# 03_CORE_BOARD.net
KiCad netlist of a schematic drawn in Altium Designer
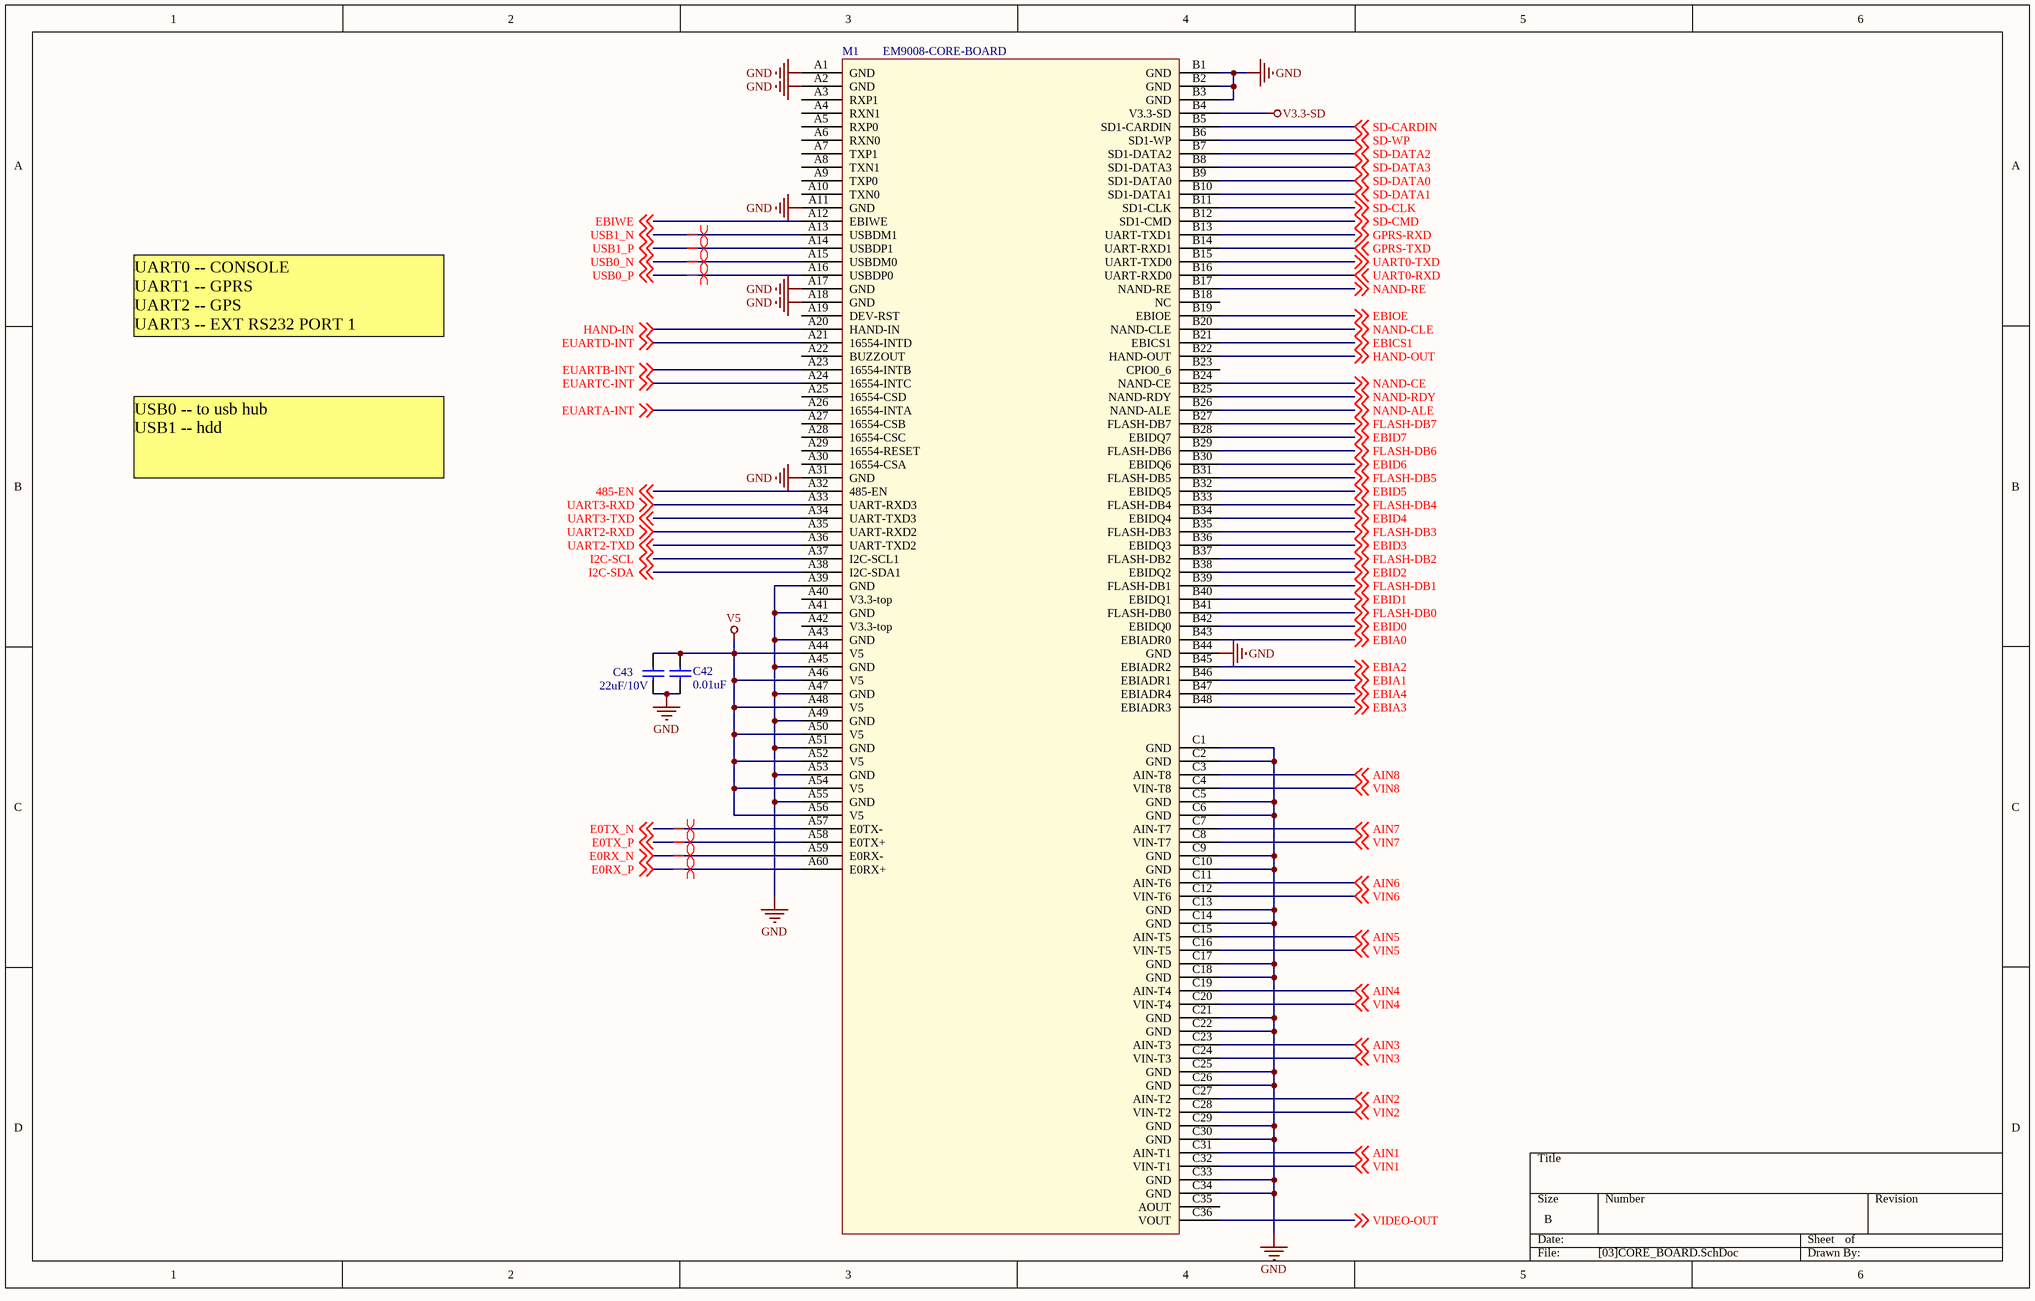
[diagram p0: [03]CORE_BOARD.SchDoc]

(export (version "E")
  (design (tool "Eeschema 10.0.6"))
  (components
    (comp (ref "C42")
      (value "0.01uF")
      (footprint "0603")
      (description "Capacitor")
      (libsource (lib "Miscellaneous Devices") (part "Cap"))
    )
    (comp (ref "C43")
      (value "22uF/10V")
      (footprint "1210")
      (description "Capacitor")
      (libsource (lib "Miscellaneous Devices") (part "Cap"))
    )
    (comp (ref "M1")
      (value "EM9008-CORE-BOARD")
      (footprint "EM9008")
      (libsource (lib "Schlib") (part "EM9008-CORE-BOARD"))
    )
  )
  (nets
    (net (code "1") (name "485-EN") (class "Default")
      (node (ref "M1") (pin "A32") (pinfunction "485-EN_A32") (pintype "passive"))
    )
    (net (code "2") (name "AIN1") (class "Default")
      (node (ref "M1") (pin "C31") (pinfunction "AIN-T1_C31") (pintype "passive"))
    )
    (net (code "3") (name "AIN2") (class "Default")
      (node (ref "M1") (pin "C27") (pinfunction "AIN-T2_C27") (pintype "passive"))
    )
    (net (code "4") (name "AIN3") (class "Default")
      (node (ref "M1") (pin "C23") (pinfunction "AIN-T3_C23") (pintype "passive"))
    )
    (net (code "5") (name "AIN4") (class "Default")
      (node (ref "M1") (pin "C19") (pinfunction "AIN-T4_C19") (pintype "passive"))
    )
    (net (code "6") (name "AIN5") (class "Default")
      (node (ref "M1") (pin "C15") (pinfunction "AIN-T5_C15") (pintype "passive"))
    )
    (net (code "7") (name "AIN6") (class "Default")
      (node (ref "M1") (pin "C11") (pinfunction "AIN-T6_C11") (pintype "passive"))
    )
    (net (code "8") (name "AIN7") (class "Default")
      (node (ref "M1") (pin "C7") (pinfunction "AIN-T7_C7") (pintype "passive"))
    )
    (net (code "9") (name "AIN8") (class "Default")
      (node (ref "M1") (pin "C3") (pinfunction "AIN-T8_C3") (pintype "passive"))
    )
    (net (code "10") (name "E0RX_N") (class "Default")
      (node (ref "M1") (pin "A59") (pinfunction "E0RX-_A59") (pintype "passive"))
    )
    (net (code "11") (name "E0RX_P") (class "Default")
      (node (ref "M1") (pin "A60") (pinfunction "E0RX+_A60") (pintype "passive"))
    )
    (net (code "12") (name "E0TX_N") (class "Default")
      (node (ref "M1") (pin "A57") (pinfunction "E0TX-_A57") (pintype "passive"))
    )
    (net (code "13") (name "E0TX_P") (class "Default")
      (node (ref "M1") (pin "A58") (pinfunction "E0TX+_A58") (pintype "passive"))
    )
    (net (code "14") (name "EBIA0") (class "Default")
      (node (ref "M1") (pin "B43") (pinfunction "EBIADR0_B43") (pintype "passive"))
    )
    (net (code "15") (name "EBIA1") (class "Default")
      (node (ref "M1") (pin "B46") (pinfunction "EBIADR1_B46") (pintype "passive"))
    )
    (net (code "16") (name "EBIA2") (class "Default")
      (node (ref "M1") (pin "B45") (pinfunction "EBIADR2_B45") (pintype "passive"))
    )
    (net (code "17") (name "EBIA3") (class "Default")
      (node (ref "M1") (pin "B48") (pinfunction "EBIADR3_B48") (pintype "passive"))
    )
    (net (code "18") (name "EBIA4") (class "Default")
      (node (ref "M1") (pin "B47") (pinfunction "EBIADR4_B47") (pintype "passive"))
    )
    (net (code "19") (name "EBICS1") (class "Default")
      (node (ref "M1") (pin "B21") (pinfunction "EBICS1_B21") (pintype "passive"))
    )
    (net (code "20") (name "EBID0") (class "Default")
      (node (ref "M1") (pin "B42") (pinfunction "EBIDQ0_B42") (pintype "passive"))
    )
    (net (code "21") (name "EBID1") (class "Default")
      (node (ref "M1") (pin "B40") (pinfunction "EBIDQ1_B40") (pintype "passive"))
    )
    (net (code "22") (name "EBID2") (class "Default")
      (node (ref "M1") (pin "B38") (pinfunction "EBIDQ2_B38") (pintype "passive"))
    )
    (net (code "23") (name "EBID3") (class "Default")
      (node (ref "M1") (pin "B36") (pinfunction "EBIDQ3_B36") (pintype "passive"))
    )
    (net (code "24") (name "EBID4") (class "Default")
      (node (ref "M1") (pin "B34") (pinfunction "EBIDQ4_B34") (pintype "passive"))
    )
    (net (code "25") (name "EBID5") (class "Default")
      (node (ref "M1") (pin "B32") (pinfunction "EBIDQ5_B32") (pintype "passive"))
    )
    (net (code "26") (name "EBID6") (class "Default")
      (node (ref "M1") (pin "B30") (pinfunction "EBIDQ6_B30") (pintype "passive"))
    )
    (net (code "27") (name "EBID7") (class "Default")
      (node (ref "M1") (pin "B28") (pinfunction "EBIDQ7_B28") (pintype "passive"))
    )
    (net (code "28") (name "EBIOE") (class "Default")
      (node (ref "M1") (pin "B19") (pinfunction "EBIOE_B19") (pintype "passive"))
    )
    (net (code "29") (name "EBIWE") (class "Default")
      (node (ref "M1") (pin "A12") (pinfunction "EBIWE_A12") (pintype "passive"))
    )
    (net (code "30") (name "EUARTA-INT") (class "Default")
      (node (ref "M1") (pin "A26") (pinfunction "16554-INTA_A26") (pintype "passive"))
    )
    (net (code "31") (name "EUARTB-INT") (class "Default")
      (node (ref "M1") (pin "A23") (pinfunction "16554-INTB_A23") (pintype "passive"))
    )
    (net (code "32") (name "EUARTC-INT") (class "Default")
      (node (ref "M1") (pin "A24") (pinfunction "16554-INTC_A24") (pintype "passive"))
    )
    (net (code "33") (name "EUARTD-INT") (class "Default")
      (node (ref "M1") (pin "A21") (pinfunction "16554-INTD_A21") (pintype "passive"))
    )
    (net (code "34") (name "FLASH-DB0") (class "Default")
      (node (ref "M1") (pin "B41") (pinfunction "FLASH-DB0_B41") (pintype "passive"))
    )
    (net (code "35") (name "FLASH-DB1") (class "Default")
      (node (ref "M1") (pin "B39") (pinfunction "FLASH-DB1_B39") (pintype "passive"))
    )
    (net (code "36") (name "FLASH-DB2") (class "Default")
      (node (ref "M1") (pin "B37") (pinfunction "FLASH-DB2_B37") (pintype "passive"))
    )
    (net (code "37") (name "FLASH-DB3") (class "Default")
      (node (ref "M1") (pin "B35") (pinfunction "FLASH-DB3_B35") (pintype "passive"))
    )
    (net (code "38") (name "FLASH-DB4") (class "Default")
      (node (ref "M1") (pin "B33") (pinfunction "FLASH-DB4_B33") (pintype "passive"))
    )
    (net (code "39") (name "FLASH-DB5") (class "Default")
      (node (ref "M1") (pin "B31") (pinfunction "FLASH-DB5_B31") (pintype "passive"))
    )
    (net (code "40") (name "FLASH-DB6") (class "Default")
      (node (ref "M1") (pin "B29") (pinfunction "FLASH-DB6_B29") (pintype "passive"))
    )
    (net (code "41") (name "FLASH-DB7") (class "Default")
      (node (ref "M1") (pin "B27") (pinfunction "FLASH-DB7_B27") (pintype "passive"))
    )
    (net (code "42") (name "GND") (class "Default")
      (node (ref "C42") (pin "1") (pinfunction "1_1") (pintype "passive"))
      (node (ref "C43") (pin "1") (pinfunction "1_1") (pintype "passive"))
      (node (ref "M1") (pin "A1") (pinfunction "GND_A1") (pintype "passive"))
      (node (ref "M1") (pin "A11") (pinfunction "GND_A11") (pintype "passive"))
      (node (ref "M1") (pin "A17") (pinfunction "GND_A17") (pintype "passive"))
      (node (ref "M1") (pin "A18") (pinfunction "GND_A18") (pintype "passive"))
      (node (ref "M1") (pin "A2") (pinfunction "GND_A2") (pintype "passive"))
      (node (ref "M1") (pin "A31") (pinfunction "GND_A31") (pintype "passive"))
      (node (ref "M1") (pin "A39") (pinfunction "GND_A39") (pintype "passive"))
      (node (ref "M1") (pin "A41") (pinfunction "GND_A41") (pintype "passive"))
      (node (ref "M1") (pin "A43") (pinfunction "GND_A43") (pintype "passive"))
      (node (ref "M1") (pin "A45") (pinfunction "GND_A45") (pintype "passive"))
      (node (ref "M1") (pin "A47") (pinfunction "GND_A47") (pintype "passive"))
      (node (ref "M1") (pin "A49") (pinfunction "GND_A49") (pintype "passive"))
      (node (ref "M1") (pin "A51") (pinfunction "GND_A51") (pintype "passive"))
      (node (ref "M1") (pin "A53") (pinfunction "GND_A53") (pintype "passive"))
      (node (ref "M1") (pin "A55") (pinfunction "GND_A55") (pintype "passive"))
      (node (ref "M1") (pin "B1") (pinfunction "GND_B1") (pintype "passive"))
      (node (ref "M1") (pin "B2") (pinfunction "GND_B2") (pintype "passive"))
      (node (ref "M1") (pin "B3") (pinfunction "GND_B3") (pintype "passive"))
      (node (ref "M1") (pin "B44") (pinfunction "GND_B44") (pintype "passive"))
      (node (ref "M1") (pin "C1") (pinfunction "GND_C1") (pintype "passive"))
      (node (ref "M1") (pin "C10") (pinfunction "GND_C10") (pintype "passive"))
      (node (ref "M1") (pin "C13") (pinfunction "GND_C13") (pintype "passive"))
      (node (ref "M1") (pin "C14") (pinfunction "GND_C14") (pintype "passive"))
      (node (ref "M1") (pin "C17") (pinfunction "GND_C17") (pintype "passive"))
      (node (ref "M1") (pin "C18") (pinfunction "GND_C18") (pintype "passive"))
      (node (ref "M1") (pin "C2") (pinfunction "GND_C2") (pintype "passive"))
      (node (ref "M1") (pin "C21") (pinfunction "GND_C21") (pintype "passive"))
      (node (ref "M1") (pin "C22") (pinfunction "GND_C22") (pintype "passive"))
      (node (ref "M1") (pin "C25") (pinfunction "GND_C25") (pintype "passive"))
      (node (ref "M1") (pin "C26") (pinfunction "GND_C26") (pintype "passive"))
      (node (ref "M1") (pin "C29") (pinfunction "GND_C29") (pintype "passive"))
      (node (ref "M1") (pin "C30") (pinfunction "GND_C30") (pintype "passive"))
      (node (ref "M1") (pin "C33") (pinfunction "GND_C33") (pintype "passive"))
      (node (ref "M1") (pin "C34") (pinfunction "GND_C34") (pintype "passive"))
      (node (ref "M1") (pin "C5") (pinfunction "GND_C5") (pintype "passive"))
      (node (ref "M1") (pin "C6") (pinfunction "GND_C6") (pintype "passive"))
      (node (ref "M1") (pin "C9") (pinfunction "GND_C9") (pintype "passive"))
    )
    (net (code "43") (name "GPRS-RXD") (class "Default")
      (node (ref "M1") (pin "B13") (pinfunction "UART-TXD1_B13") (pintype "passive"))
    )
    (net (code "44") (name "GPRS-TXD") (class "Default")
      (node (ref "M1") (pin "B14") (pinfunction "UART-RXD1_B14") (pintype "passive"))
    )
    (net (code "45") (name "HAND-IN") (class "Default")
      (node (ref "M1") (pin "A20") (pinfunction "HAND-IN_A20") (pintype "passive"))
    )
    (net (code "46") (name "HAND-OUT") (class "Default")
      (node (ref "M1") (pin "B22") (pinfunction "HAND-OUT_B22") (pintype "passive"))
    )
    (net (code "47") (name "I2C-SCL") (class "Default")
      (node (ref "M1") (pin "A37") (pinfunction "I2C-SCL1_A37") (pintype "passive"))
    )
    (net (code "48") (name "I2C-SDA") (class "Default")
      (node (ref "M1") (pin "A38") (pinfunction "I2C-SDA1_A38") (pintype "passive"))
    )
    (net (code "49") (name "NAND-ALE") (class "Default")
      (node (ref "M1") (pin "B26") (pinfunction "NAND-ALE_B26") (pintype "passive"))
    )
    (net (code "50") (name "NAND-CE") (class "Default")
      (node (ref "M1") (pin "B24") (pinfunction "NAND-CE_B24") (pintype "passive"))
    )
    (net (code "51") (name "NAND-CLE") (class "Default")
      (node (ref "M1") (pin "B20") (pinfunction "NAND-CLE_B20") (pintype "passive"))
    )
    (net (code "52") (name "NAND-RDY") (class "Default")
      (node (ref "M1") (pin "B25") (pinfunction "NAND-RDY_B25") (pintype "passive"))
    )
    (net (code "53") (name "NAND-RE") (class "Default")
      (node (ref "M1") (pin "B17") (pinfunction "NAND-RE_B17") (pintype "passive"))
    )
    (net (code "54") (name "SD-CARDIN") (class "Default")
      (node (ref "M1") (pin "B5") (pinfunction "SD1-CARDIN_B5") (pintype "passive"))
    )
    (net (code "55") (name "SD-CLK") (class "Default")
      (node (ref "M1") (pin "B11") (pinfunction "SD1-CLK_B11") (pintype "passive"))
    )
    (net (code "56") (name "SD-CMD") (class "Default")
      (node (ref "M1") (pin "B12") (pinfunction "SD1-CMD_B12") (pintype "passive"))
    )
    (net (code "57") (name "SD-DATA0") (class "Default")
      (node (ref "M1") (pin "B9") (pinfunction "SD1-DATA0_B9") (pintype "passive"))
    )
    (net (code "58") (name "SD-DATA1") (class "Default")
      (node (ref "M1") (pin "B10") (pinfunction "SD1-DATA1_B10") (pintype "passive"))
    )
    (net (code "59") (name "SD-DATA2") (class "Default")
      (node (ref "M1") (pin "B7") (pinfunction "SD1-DATA2_B7") (pintype "passive"))
    )
    (net (code "60") (name "SD-DATA3") (class "Default")
      (node (ref "M1") (pin "B8") (pinfunction "SD1-DATA3_B8") (pintype "passive"))
    )
    (net (code "61") (name "SD-WP") (class "Default")
      (node (ref "M1") (pin "B6") (pinfunction "SD1-WP_B6") (pintype "passive"))
    )
    (net (code "62") (name "UART0-RXD") (class "Default")
      (node (ref "M1") (pin "B16") (pinfunction "UART-RXD0_B16") (pintype "passive"))
    )
    (net (code "63") (name "UART0-TXD") (class "Default")
      (node (ref "M1") (pin "B15") (pinfunction "UART-TXD0_B15") (pintype "passive"))
    )
    (net (code "64") (name "UART2-RXD") (class "Default")
      (node (ref "M1") (pin "A35") (pinfunction "UART-RXD2_A35") (pintype "passive"))
    )
    (net (code "65") (name "UART2-TXD") (class "Default")
      (node (ref "M1") (pin "A36") (pinfunction "UART-TXD2_A36") (pintype "passive"))
    )
    (net (code "66") (name "UART3-RXD") (class "Default")
      (node (ref "M1") (pin "A33") (pinfunction "UART-RXD3_A33") (pintype "passive"))
    )
    (net (code "67") (name "UART3-TXD") (class "Default")
      (node (ref "M1") (pin "A34") (pinfunction "UART-TXD3_A34") (pintype "passive"))
    )
    (net (code "68") (name "USB0_N") (class "Default")
      (node (ref "M1") (pin "A15") (pinfunction "USBDM0_A15") (pintype "passive"))
    )
    (net (code "69") (name "USB0_P") (class "Default")
      (node (ref "M1") (pin "A16") (pinfunction "USBDP0_A16") (pintype "passive"))
    )
    (net (code "70") (name "USB1_N") (class "Default")
      (node (ref "M1") (pin "A13") (pinfunction "USBDM1_A13") (pintype "passive"))
    )
    (net (code "71") (name "USB1_P") (class "Default")
      (node (ref "M1") (pin "A14") (pinfunction "USBDP1_A14") (pintype "passive"))
    )
    (net (code "72") (name "V3.3-SD") (class "Default")
      (node (ref "M1") (pin "B4") (pinfunction "V3.3-SD_B4") (pintype "passive"))
    )
    (net (code "73") (name "V5") (class "Default")
      (node (ref "C42") (pin "2") (pinfunction "2_2") (pintype "passive"))
      (node (ref "C43") (pin "2") (pinfunction "2_2") (pintype "passive"))
      (node (ref "M1") (pin "A44") (pinfunction "V5_A44") (pintype "passive"))
      (node (ref "M1") (pin "A46") (pinfunction "V5_A46") (pintype "passive"))
      (node (ref "M1") (pin "A48") (pinfunction "V5_A48") (pintype "passive"))
      (node (ref "M1") (pin "A50") (pinfunction "V5_A50") (pintype "passive"))
      (node (ref "M1") (pin "A52") (pinfunction "V5_A52") (pintype "passive"))
      (node (ref "M1") (pin "A54") (pinfunction "V5_A54") (pintype "passive"))
      (node (ref "M1") (pin "A56") (pinfunction "V5_A56") (pintype "passive"))
    )
    (net (code "74") (name "VIDEO-OUT") (class "Default")
      (node (ref "M1") (pin "C36") (pinfunction "VOUT_C36") (pintype "passive"))
    )
    (net (code "75") (name "VIN1") (class "Default")
      (node (ref "M1") (pin "C32") (pinfunction "VIN-T1_C32") (pintype "passive"))
    )
    (net (code "76") (name "VIN2") (class "Default")
      (node (ref "M1") (pin "C28") (pinfunction "VIN-T2_C28") (pintype "passive"))
    )
    (net (code "77") (name "VIN3") (class "Default")
      (node (ref "M1") (pin "C24") (pinfunction "VIN-T3_C24") (pintype "passive"))
    )
    (net (code "78") (name "VIN4") (class "Default")
      (node (ref "M1") (pin "C20") (pinfunction "VIN-T4_C20") (pintype "passive"))
    )
    (net (code "79") (name "VIN5") (class "Default")
      (node (ref "M1") (pin "C16") (pinfunction "VIN-T5_C16") (pintype "passive"))
    )
    (net (code "80") (name "VIN6") (class "Default")
      (node (ref "M1") (pin "C12") (pinfunction "VIN-T6_C12") (pintype "passive"))
    )
    (net (code "81") (name "VIN7") (class "Default")
      (node (ref "M1") (pin "C8") (pinfunction "VIN-T7_C8") (pintype "passive"))
    )
    (net (code "82") (name "VIN8") (class "Default")
      (node (ref "M1") (pin "C4") (pinfunction "VIN-T8_C4") (pintype "passive"))
    )
    (net (code "83") (name "unconnected-(M1-16554-CSA-PadA30)") (class "Default")
      (node (ref "M1") (pin "A30") (pinfunction "16554-CSA_A30") (pintype "passive"))
    )
    (net (code "84") (name "unconnected-(M1-16554-CSB-PadA27)") (class "Default")
      (node (ref "M1") (pin "A27") (pinfunction "16554-CSB_A27") (pintype "passive"))
    )
    (net (code "85") (name "unconnected-(M1-16554-CSC-PadA28)") (class "Default")
      (node (ref "M1") (pin "A28") (pinfunction "16554-CSC_A28") (pintype "passive"))
    )
    (net (code "86") (name "unconnected-(M1-16554-CSD-PadA25)") (class "Default")
      (node (ref "M1") (pin "A25") (pinfunction "16554-CSD_A25") (pintype "passive"))
    )
    (net (code "87") (name "unconnected-(M1-16554-RESET-PadA29)") (class "Default")
      (node (ref "M1") (pin "A29") (pinfunction "16554-RESET_A29") (pintype "passive"))
    )
    (net (code "88") (name "unconnected-(M1-AOUT-PadC35)") (class "Default")
      (node (ref "M1") (pin "C35") (pinfunction "AOUT_C35") (pintype "passive"))
    )
    (net (code "89") (name "unconnected-(M1-BUZZOUT-PadA22)") (class "Default")
      (node (ref "M1") (pin "A22") (pinfunction "BUZZOUT_A22") (pintype "passive"))
    )
    (net (code "90") (name "unconnected-(M1-CPIO0_6-PadB23)") (class "Default")
      (node (ref "M1") (pin "B23") (pinfunction "CPIO0_6_B23") (pintype "passive"))
    )
    (net (code "91") (name "unconnected-(M1-DEV-RST-PadA19)") (class "Default")
      (node (ref "M1") (pin "A19") (pinfunction "DEV-RST_A19") (pintype "passive"))
    )
    (net (code "92") (name "unconnected-(M1-NC-PadB18)") (class "Default")
      (node (ref "M1") (pin "B18") (pinfunction "NC_B18") (pintype "passive"))
    )
    (net (code "93") (name "unconnected-(M1-RXN0-PadA6)") (class "Default")
      (node (ref "M1") (pin "A6") (pinfunction "RXN0_A6") (pintype "passive"))
    )
    (net (code "94") (name "unconnected-(M1-RXN1-PadA4)") (class "Default")
      (node (ref "M1") (pin "A4") (pinfunction "RXN1_A4") (pintype "passive"))
    )
    (net (code "95") (name "unconnected-(M1-RXP0-PadA5)") (class "Default")
      (node (ref "M1") (pin "A5") (pinfunction "RXP0_A5") (pintype "passive"))
    )
    (net (code "96") (name "unconnected-(M1-RXP1-PadA3)") (class "Default")
      (node (ref "M1") (pin "A3") (pinfunction "RXP1_A3") (pintype "passive"))
    )
    (net (code "97") (name "unconnected-(M1-TXN0-PadA10)") (class "Default")
      (node (ref "M1") (pin "A10") (pinfunction "TXN0_A10") (pintype "passive"))
    )
    (net (code "98") (name "unconnected-(M1-TXN1-PadA8)") (class "Default")
      (node (ref "M1") (pin "A8") (pinfunction "TXN1_A8") (pintype "passive"))
    )
    (net (code "99") (name "unconnected-(M1-TXP0-PadA9)") (class "Default")
      (node (ref "M1") (pin "A9") (pinfunction "TXP0_A9") (pintype "passive"))
    )
    (net (code "100") (name "unconnected-(M1-TXP1-PadA7)") (class "Default")
      (node (ref "M1") (pin "A7") (pinfunction "TXP1_A7") (pintype "passive"))
    )
    (net (code "101") (name "unconnected-(M1-V3.3-top-PadA40)") (class "Default")
      (node (ref "M1") (pin "A40") (pinfunction "V3.3-top_A40") (pintype "passive"))
    )
    (net (code "102") (name "unconnected-(M1-V3.3-top-PadA42)") (class "Default")
      (node (ref "M1") (pin "A42") (pinfunction "V3.3-top_A42") (pintype "passive"))
    )
  )
)
